# minM3car.net
KiCad netlist of a schematic drawn in EAGLE
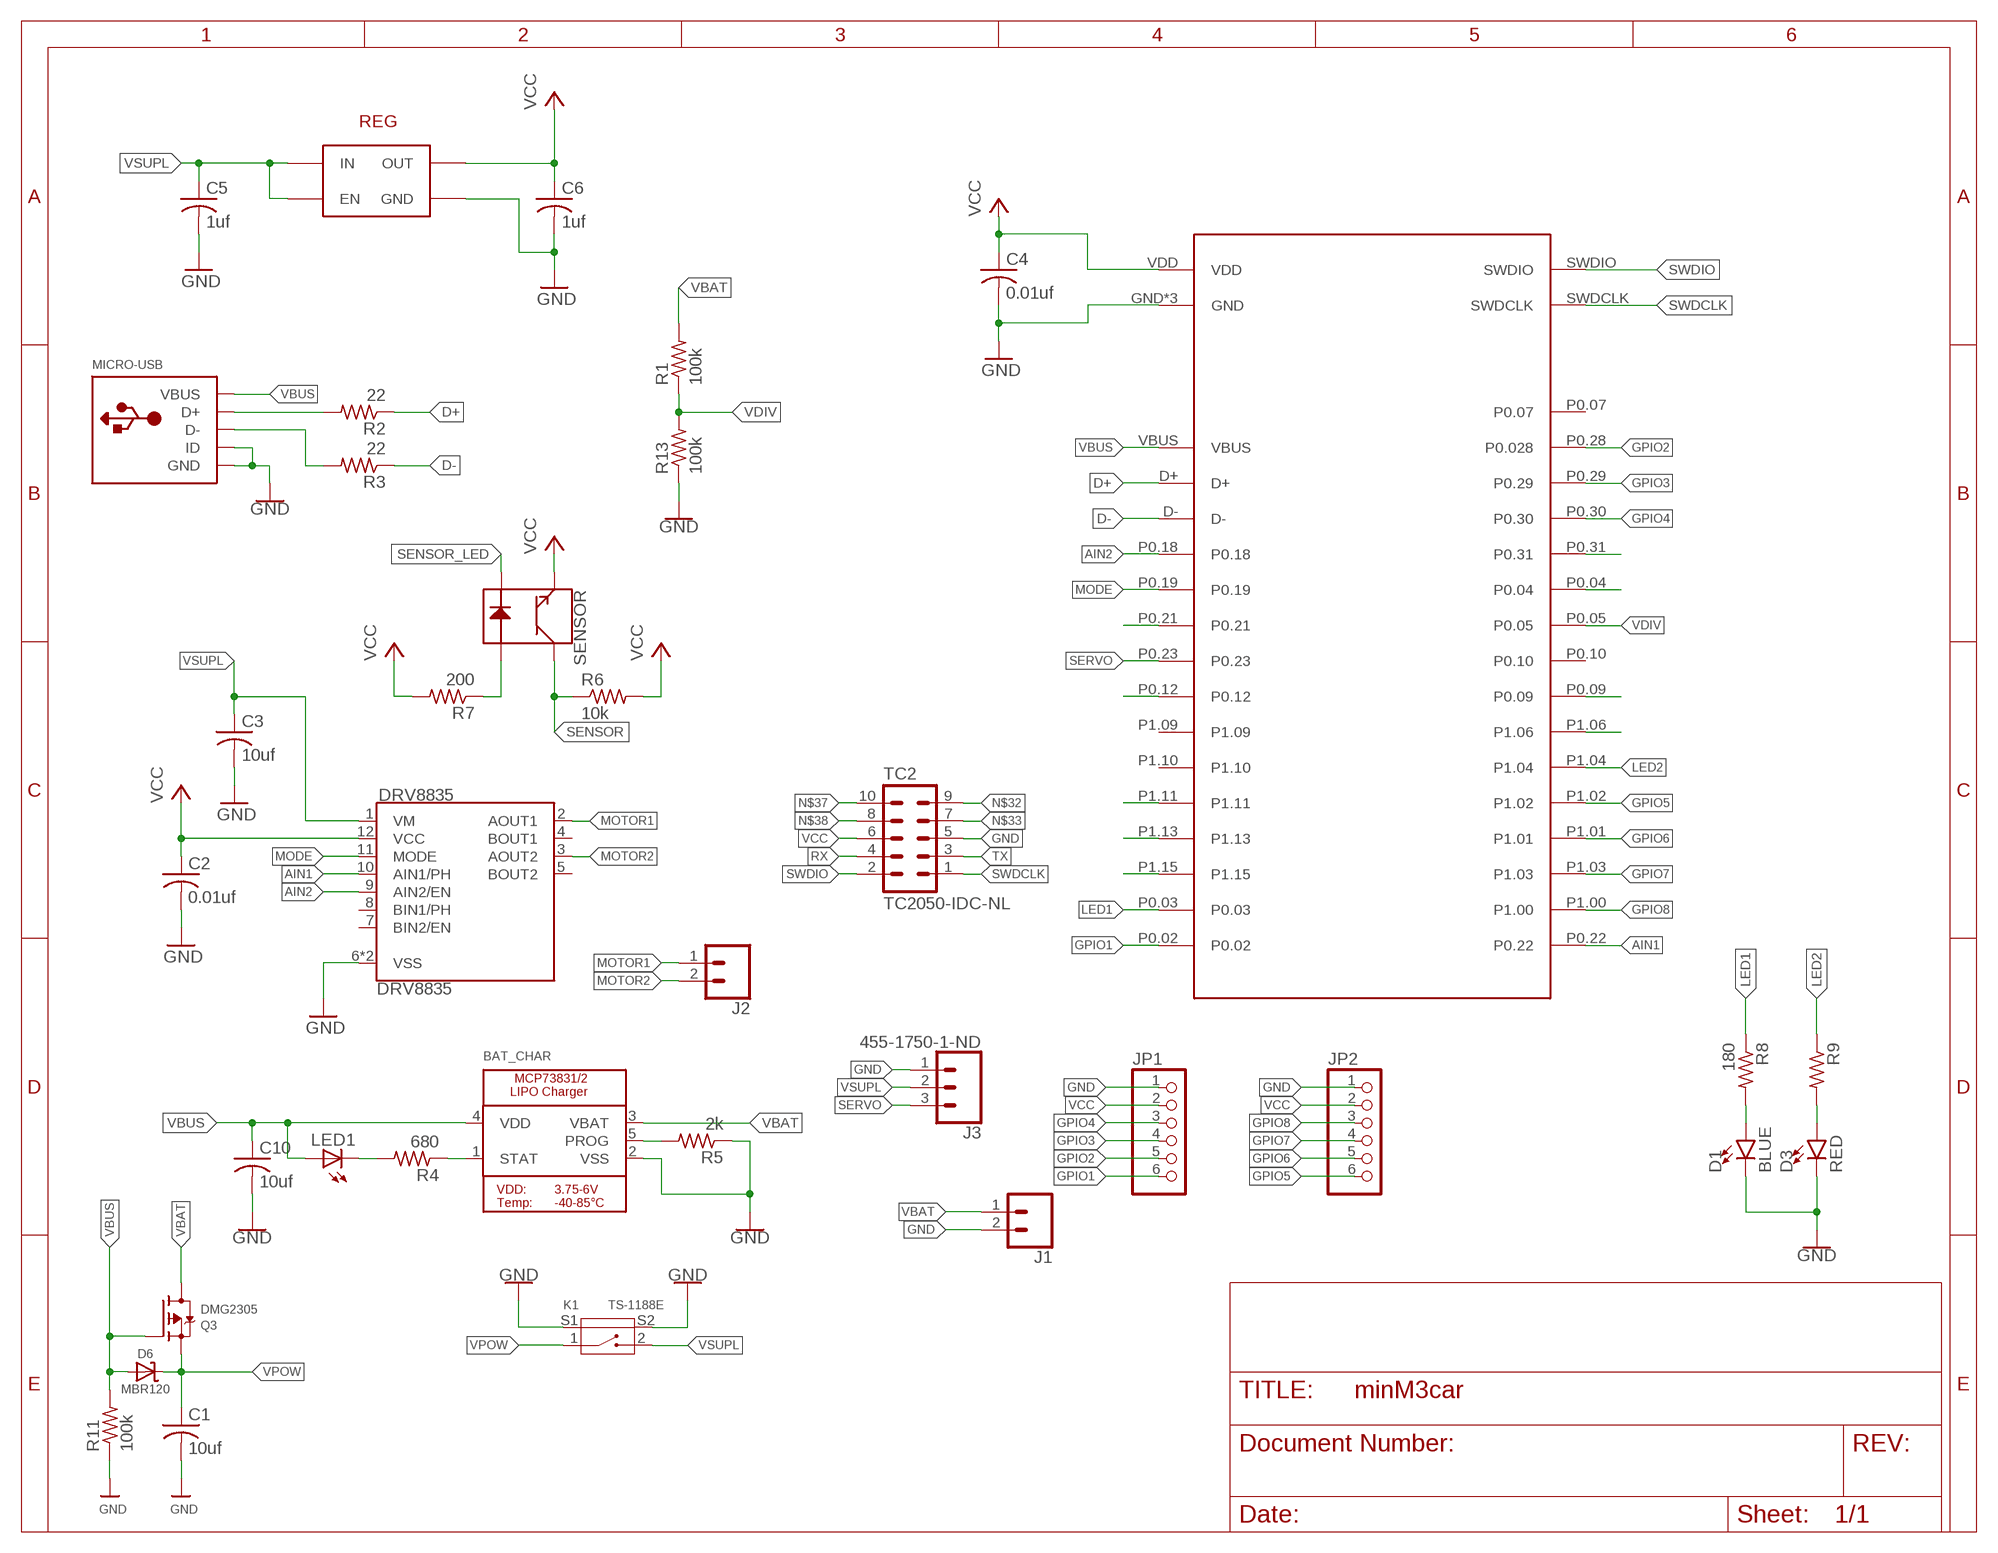
[diagram p0: schematic, sheet 1]

(export (version "E")
  (design (tool "Eeschema 10.0.6"))
  (components
    (comp (ref "BAT_CHAR")
      (value "MICROBUILDER_MCP73831/2")
      (footprint "eagle-import:MICROBUILDER_SOT23-5")
      (fields (field (name "MPN") " MCP73831T-2ACI/OT"))
      (libsource (lib "eagle-import") (part "MICROBUILDER_MCP73831/2"))
    )
    (comp (ref "C1")
      (value "10uf")
      (footprint "eagle-import:C0402")
      (fields (field (name "MPN") "GRM155R60G106ME44D"))
      (libsource (lib "eagle-import") (part "C-USC0402"))
    )
    (comp (ref "C2")
      (value "0.01uf")
      (footprint "eagle-import:C0402")
      (fields (field (name "MPN") "CL05C100JB5NNNC"))
      (libsource (lib "eagle-import") (part "C-USC0402"))
    )
    (comp (ref "C3")
      (value "10uf")
      (footprint "eagle-import:C0402")
      (fields (field (name "MPN") "GRM155R60G106ME44D"))
      (libsource (lib "eagle-import") (part "C-USC0402"))
    )
    (comp (ref "C4")
      (value "0.01uf")
      (footprint "eagle-import:C0402")
      (fields (field (name "MPN") "CL05C100JB5NNNC"))
      (libsource (lib "eagle-import") (part "C-USC0402"))
    )
    (comp (ref "C5")
      (value "1uf")
      (footprint "eagle-import:C0402")
      (fields (field (name "MPN") "CL05A105KP5NNNC"))
      (libsource (lib "eagle-import") (part "C-USC0402"))
    )
    (comp (ref "C6")
      (value "1uf")
      (footprint "eagle-import:C0402")
      (fields (field (name "MPN") "CL05A105KP5NNNC"))
      (libsource (lib "eagle-import") (part "C-USC0402"))
    )
    (comp (ref "C10")
      (value "10uf")
      (footprint "eagle-import:C0402")
      (fields (field (name "MPN") "GRM155R60G106ME44D"))
      (libsource (lib "eagle-import") (part "C-USC0402"))
    )
    (comp (ref "D1")
      (value "BLUE")
      (footprint "eagle-import:LED-0603")
      (fields (field (name "MPN") "150060YS75000"))
      (libsource (lib "eagle-import") (part "LED-BLUE0603"))
    )
    (comp (ref "D3")
      (value "RED")
      (footprint "eagle-import:LED-0603")
      (fields (field (name "MPN") "150060YS75000"))
      (libsource (lib "eagle-import") (part "LED-RED0603"))
    )
    (comp (ref "D6")
      (value "MBR120")
      (footprint "eagle-import:SOD-123")
      (fields (field (name "MPN") "MBR120VLSFT3G"))
      (libsource (lib "eagle-import") (part "DIODE-SCHOTTKYSOD-123"))
    )
    (comp (ref "DRV8835")
      (value "DRV8835")
      (footprint "eagle-import:WSON-12")
      (fields (field (name "MPN") "DRV8835DSSR"))
      (libsource (lib "eagle-import") (part "DRV883X"))
    )
    (comp (ref "J1")
      (value "CONN_02")
      (footprint "eagle-import:1X02")
      (libsource (lib "eagle-import") (part "CONN_02"))
    )
    (comp (ref "J2")
      (value "CONN_02")
      (footprint "eagle-import:1X02")
      (libsource (lib "eagle-import") (part "CONN_02"))
    )
    (comp (ref "J3")
      (value "455-1750-1-ND")
      (footprint "eagle-import:1X03")
      (libsource (lib "eagle-import") (part "CONN_03"))
    )
    (comp (ref "JP1")
      (value "PINHD-1X6")
      (footprint "eagle-import:1X06")
      (libsource (lib "eagle-import") (part "PINHD-1X6"))
    )
    (comp (ref "JP2")
      (value "PINHD-1X6")
      (footprint "eagle-import:1X06")
      (libsource (lib "eagle-import") (part "PINHD-1X6"))
    )
    (comp (ref "K1")
      (value "TS-1188E")
      (footprint "eagle-import:SW4-SMD-7.0X3.5X3.5MM-90D")
      (libsource (lib "eagle-import") (part "SMD-BUTTON(2+2P-7X3.5MM-90D)"))
    )
    (comp (ref "LED1")
      (value "LEDCHIPLED_0603")
      (footprint "eagle-import:CHIPLED_0603")
      (fields (field (name "MPN") "150060GS75000"))
      (libsource (lib "eagle-import") (part "LEDCHIPLED_0603"))
    )
    (comp (ref "MICRO-USB")
      (value "MICROBUILDER_USB_MICRO_20329_V2")
      (footprint "eagle-import:MICROBUILDER_4UCONN_20329_V2")
      (fields (field (name "MPN") "10103592-0001LF "))
      (libsource (lib "eagle-import") (part "MICROBUILDER_USB_MICRO_20329_V2"))
    )
    (comp (ref "NRF52")
      (value "HOLYIOT")
      (footprint "eagle-import:HOLYIOT")
      (fields (field (name "MPN") "113990556"))
      (libsource (lib "eagle-import") (part "HOLYIOT"))
    )
    (comp (ref "Q3")
      (value "DMG2305")
      (footprint "eagle-import:SOT23-R")
      (fields (field (name "MPN") "DMG2305UXQ-7"))
      (libsource (lib "eagle-import") (part "MOSFET-P"))
    )
    (comp (ref "R1")
      (value "100k")
      (footprint "eagle-import:R0402")
      (fields (field (name "MPN") "RC0402JR-07100KL"))
      (libsource (lib "eagle-import") (part "adafruit_420_R-US_R0402"))
    )
    (comp (ref "R2")
      (value "22")
      (footprint "eagle-import:R0402")
      (fields (field (name "MPN") "BLM15BB220SN1D"))
      (libsource (lib "eagle-import") (part "R-US_R0402"))
    )
    (comp (ref "R3")
      (value "22")
      (footprint "eagle-import:R0402")
      (fields (field (name "MPN") "BLM15BB220SN1D"))
      (libsource (lib "eagle-import") (part "R-US_R0402"))
    )
    (comp (ref "R4")
      (value "680")
      (footprint "eagle-import:R0402")
      (fields (field (name "MPN") "RC0402JR-07680RL"))
      (libsource (lib "eagle-import") (part "R-US_R0402"))
    )
    (comp (ref "R5")
      (value "2k")
      (footprint "eagle-import:R0402")
      (fields (field (name "MPN") "RC0402FR-072KL"))
      (libsource (lib "eagle-import") (part "R-US_R0402"))
    )
    (comp (ref "R6")
      (value "10k")
      (footprint "eagle-import:R0402")
      (fields (field (name "MPN") "RC0402JR-0710KL"))
      (libsource (lib "eagle-import") (part "R-US_R0402"))
    )
    (comp (ref "R7")
      (value "200")
      (footprint "eagle-import:R0402")
      (fields (field (name "MPN") "0402WGF2000TCE"))
      (libsource (lib "eagle-import") (part "R-US_R0402"))
    )
    (comp (ref "R8")
      (value "180")
      (footprint "eagle-import:R0402")
      (fields (field (name "MPN") "RC0402FR-07180RL"))
      (libsource (lib "eagle-import") (part "R-US_R0402"))
    )
    (comp (ref "R9")
      (value "180")
      (footprint "eagle-import:R0402")
      (fields (field (name "MPN") "RC0402FR-07180RL"))
      (libsource (lib "eagle-import") (part "R-US_R0402"))
    )
    (comp (ref "R11")
      (value "100k")
      (footprint "eagle-import:R0402")
      (fields (field (name "MPN") "RC0402JR-07100KL"))
      (libsource (lib "eagle-import") (part "adafruit_420_R-US_R0402"))
    )
    (comp (ref "R13")
      (value "100k")
      (footprint "eagle-import:R0402")
      (fields (field (name "MPN") "RC0402JR-07100KL"))
      (libsource (lib "eagle-import") (part "adafruit_420_R-US_R0402"))
    )
    (comp (ref "REG")
      (value "TLV703")
      (footprint "eagle-import:SOT95P285X120-5N")
      (fields (field (name "MPN") "TLV7031DBVR"))
      (libsource (lib "eagle-import") (part "TLV703"))
    )
    (comp (ref "SENSOR")
      (value "QRE1113SMD-W")
      (footprint "eagle-import:QRE1113-W")
      (fields (field (name "MPN") "QRE1113GR"))
      (libsource (lib "eagle-import") (part "QRE1113SMD-W"))
    )
    (comp (ref "TC2")
      (value "TC2050-IDC-NL")
      (footprint "eagle-import:TC2050-IDC-NL")
      (libsource (lib "eagle-import") (part "TC2050-IDC-NL"))
    )
  )
  (nets
    (net (code "1") (name "AIN1") (class "Default")
      (node (ref "DRV8835") (pin "10") (pinfunction "AIN1/PH_10") (pintype "bidirectional"))
      (node (ref "NRF52") (pin "P0.22") (pinfunction "P0.22_P0.22") (pintype "bidirectional"))
    )
    (net (code "2") (name "AIN2") (class "Default")
      (node (ref "DRV8835") (pin "9") (pinfunction "AIN2/EN_9") (pintype "bidirectional"))
      (node (ref "NRF52") (pin "P0.18") (pinfunction "P0.18_P0.18") (pintype "bidirectional"))
    )
    (net (code "3") (name "D+") (class "Default")
      (node (ref "NRF52") (pin "D+") (pinfunction "D+_D+") (pintype "bidirectional"))
      (node (ref "R2") (pin "1") (pinfunction "1_1") (pintype "passive"))
    )
    (net (code "4") (name "D-") (class "Default")
      (node (ref "NRF52") (pin "D-") (pinfunction "D-_D-") (pintype "bidirectional"))
      (node (ref "R3") (pin "1") (pinfunction "1_1") (pintype "passive"))
    )
    (net (code "5") (name "GND") (class "Default")
      (node (ref "BAT_CHAR") (pin "2") (pinfunction "VSS_2") (pintype "power_in"))
      (node (ref "C1") (pin "2") (pinfunction "2_2") (pintype "passive"))
      (node (ref "C10") (pin "2") (pinfunction "2_2") (pintype "passive"))
      (node (ref "C2") (pin "2") (pinfunction "2_2") (pintype "passive"))
      (node (ref "C3") (pin "2") (pinfunction "2_2") (pintype "passive"))
      (node (ref "C4") (pin "2") (pinfunction "2_2") (pintype "passive"))
      (node (ref "C5") (pin "2") (pinfunction "2_2") (pintype "passive"))
      (node (ref "C6") (pin "2") (pinfunction "2_2") (pintype "passive"))
      (node (ref "D1") (pin "C") (pinfunction "C_C") (pintype "passive"))
      (node (ref "D3") (pin "C") (pinfunction "C_C") (pintype "passive"))
      (node (ref "DRV8835") (pin "6") (pinfunction "VSS_6") (pintype "bidirectional"))
      (node (ref "DRV8835") (pin "PAD") (pinfunction "VSS_PAD") (pintype "bidirectional"))
      (node (ref "J1") (pin "2") (pinfunction "2_2") (pintype "passive"))
      (node (ref "J3") (pin "1") (pinfunction "1_1") (pintype "passive"))
      (node (ref "JP1") (pin "1") (pinfunction "1_1") (pintype "passive"))
      (node (ref "JP2") (pin "1") (pinfunction "1_1") (pintype "passive"))
      (node (ref "K1") (pin "S1") (pinfunction "S1_S1") (pintype "bidirectional"))
      (node (ref "K1") (pin "S2") (pinfunction "S2_S2") (pintype "bidirectional"))
      (node (ref "MICRO-USB") (pin "BASE@1") (pinfunction "GND_BASE@1") (pintype "power_in"))
      (node (ref "MICRO-USB") (pin "BASE@2") (pinfunction "GND_BASE@2") (pintype "power_in"))
      (node (ref "MICRO-USB") (pin "GND") (pinfunction "GND_GND") (pintype "power_in"))
      (node (ref "MICRO-USB") (pin "ID") (pinfunction "ID_ID") (pintype "bidirectional"))
      (node (ref "MICRO-USB") (pin "SPRT@1") (pinfunction "GND_SPRT@1") (pintype "power_in"))
      (node (ref "MICRO-USB") (pin "SPRT@2") (pinfunction "GND_SPRT@2") (pintype "power_in"))
      (node (ref "MICRO-USB") (pin "SPRT@3") (pinfunction "GND_SPRT@3") (pintype "power_in"))
      (node (ref "MICRO-USB") (pin "SPRT@4") (pinfunction "GND_SPRT@4") (pintype "power_in"))
      (node (ref "NRF52") (pin "GND") (pinfunction "GND_GND") (pintype "bidirectional"))
      (node (ref "NRF52") (pin "GND2") (pinfunction "GND_GND2") (pintype "bidirectional"))
      (node (ref "NRF52") (pin "GND3") (pinfunction "GND_GND3") (pintype "bidirectional"))
      (node (ref "R11") (pin "1") (pinfunction "1_1") (pintype "passive"))
      (node (ref "R13") (pin "1") (pinfunction "1_1") (pintype "passive"))
      (node (ref "R5") (pin "1") (pinfunction "1_1") (pintype "passive"))
      (node (ref "REG") (pin "2") (pinfunction "GND_2") (pintype "bidirectional"))
      (node (ref "TC2") (pin "5") (pinfunction "5_5") (pintype "passive"))
    )
    (net (code "6") (name "GPIO1") (class "Default")
      (node (ref "JP1") (pin "6") (pinfunction "6_6") (pintype "passive"))
      (node (ref "NRF52") (pin "P0.02") (pinfunction "P0.02_P0.02") (pintype "bidirectional"))
    )
    (net (code "7") (name "GPIO2") (class "Default")
      (node (ref "JP1") (pin "5") (pinfunction "5_5") (pintype "passive"))
      (node (ref "NRF52") (pin "P0.28") (pinfunction "P0.028_P0.28") (pintype "bidirectional"))
    )
    (net (code "8") (name "GPIO3") (class "Default")
      (node (ref "JP1") (pin "4") (pinfunction "4_4") (pintype "passive"))
      (node (ref "NRF52") (pin "P0.29") (pinfunction "P0.29_P0.29") (pintype "bidirectional"))
    )
    (net (code "9") (name "GPIO4") (class "Default")
      (node (ref "JP1") (pin "3") (pinfunction "3_3") (pintype "passive"))
      (node (ref "NRF52") (pin "P0.30") (pinfunction "P0.30_P0.30") (pintype "bidirectional"))
    )
    (net (code "10") (name "GPIO5") (class "Default")
      (node (ref "JP2") (pin "6") (pinfunction "6_6") (pintype "passive"))
      (node (ref "NRF52") (pin "P1.02") (pinfunction "P1.02_P1.02") (pintype "bidirectional"))
    )
    (net (code "11") (name "GPIO6") (class "Default")
      (node (ref "JP2") (pin "5") (pinfunction "5_5") (pintype "passive"))
      (node (ref "NRF52") (pin "P1.01") (pinfunction "P1.01_P1.01") (pintype "bidirectional"))
    )
    (net (code "12") (name "GPIO7") (class "Default")
      (node (ref "JP2") (pin "4") (pinfunction "4_4") (pintype "passive"))
      (node (ref "NRF52") (pin "P1.03") (pinfunction "P1.03_P1.03") (pintype "bidirectional"))
    )
    (net (code "13") (name "GPIO8") (class "Default")
      (node (ref "JP2") (pin "3") (pinfunction "3_3") (pintype "passive"))
      (node (ref "NRF52") (pin "P1.00") (pinfunction "P1.00_P1.00") (pintype "bidirectional"))
    )
    (net (code "14") (name "LED1") (class "Default")
      (node (ref "NRF52") (pin "P0.03") (pinfunction "P0.03_P0.03") (pintype "bidirectional"))
      (node (ref "R8") (pin "1") (pinfunction "1_1") (pintype "passive"))
    )
    (net (code "15") (name "LED2") (class "Default")
      (node (ref "NRF52") (pin "P1.04") (pinfunction "P1.04_P1.04") (pintype "bidirectional"))
      (node (ref "R9") (pin "1") (pinfunction "1_1") (pintype "passive"))
    )
    (net (code "16") (name "MODE") (class "Default")
      (node (ref "DRV8835") (pin "11") (pinfunction "MODE_11") (pintype "bidirectional"))
      (node (ref "NRF52") (pin "P0.19") (pinfunction "P0.19_P0.19") (pintype "bidirectional"))
    )
    (net (code "17") (name "MOTOR1") (class "Default")
      (node (ref "DRV8835") (pin "2") (pinfunction "AOUT1_2") (pintype "bidirectional"))
      (node (ref "J2") (pin "1") (pinfunction "1_1") (pintype "passive"))
    )
    (net (code "18") (name "MOTOR2") (class "Default")
      (node (ref "DRV8835") (pin "3") (pinfunction "AOUT2_3") (pintype "bidirectional"))
      (node (ref "J2") (pin "2") (pinfunction "2_2") (pintype "passive"))
    )
    (net (code "19") (name "N$32") (class "Default")
      (node (ref "TC2") (pin "9") (pinfunction "9_9") (pintype "passive"))
    )
    (net (code "20") (name "N$33") (class "Default")
      (node (ref "TC2") (pin "7") (pinfunction "7_7") (pintype "passive"))
    )
    (net (code "21") (name "N$37") (class "Default")
      (node (ref "TC2") (pin "10") (pinfunction "10_10") (pintype "passive"))
    )
    (net (code "22") (name "N$38") (class "Default")
      (node (ref "TC2") (pin "8") (pinfunction "8_8") (pintype "passive"))
    )
    (net (code "23") (name "Net-(BAT_CHAR-PROG)") (class "Default")
      (node (ref "BAT_CHAR") (pin "5") (pinfunction "PROG_5") (pintype "input"))
      (node (ref "R5") (pin "2") (pinfunction "2_2") (pintype "passive"))
    )
    (net (code "24") (name "Net-(BAT_CHAR-STAT)") (class "Default")
      (node (ref "BAT_CHAR") (pin "1") (pinfunction "STAT_1") (pintype "output"))
      (node (ref "R4") (pin "1") (pinfunction "1_1") (pintype "passive"))
    )
    (net (code "25") (name "Net-(D1-PadA)") (class "Default")
      (node (ref "D1") (pin "A") (pinfunction "A_A") (pintype "passive"))
      (node (ref "R8") (pin "2") (pinfunction "2_2") (pintype "passive"))
    )
    (net (code "26") (name "Net-(D3-PadA)") (class "Default")
      (node (ref "D3") (pin "A") (pinfunction "A_A") (pintype "passive"))
      (node (ref "R9") (pin "2") (pinfunction "2_2") (pintype "passive"))
    )
    (net (code "27") (name "Net-(LED1-PadC)") (class "Default")
      (node (ref "LED1") (pin "C") (pinfunction "C_C") (pintype "passive"))
      (node (ref "R4") (pin "2") (pinfunction "2_2") (pintype "passive"))
    )
    (net (code "28") (name "Net-(MICRO-USB-PadD+)") (class "Default")
      (node (ref "MICRO-USB") (pin "D+") (pinfunction "D+_D+") (pintype "bidirectional"))
      (node (ref "R2") (pin "2") (pinfunction "2_2") (pintype "passive"))
    )
    (net (code "29") (name "Net-(MICRO-USB-PadD-)") (class "Default")
      (node (ref "MICRO-USB") (pin "D-") (pinfunction "D-_D-") (pintype "bidirectional"))
      (node (ref "R3") (pin "2") (pinfunction "2_2") (pintype "passive"))
    )
    (net (code "30") (name "Net-(SENSOR-A)") (class "Default")
      (node (ref "R7") (pin "1") (pinfunction "1_1") (pintype "passive"))
      (node (ref "SENSOR") (pin "1") (pinfunction "A_1") (pintype "bidirectional"))
    )
    (net (code "31") (name "RX") (class "Default")
      (node (ref "TC2") (pin "4") (pinfunction "4_4") (pintype "passive"))
    )
    (net (code "32") (name "SENSOR") (class "Default")
      (node (ref "R6") (pin "1") (pinfunction "1_1") (pintype "passive"))
      (node (ref "SENSOR") (pin "3") (pinfunction "C_3") (pintype "bidirectional"))
    )
    (net (code "33") (name "SENSOR_LED") (class "Default")
      (node (ref "SENSOR") (pin "2") (pinfunction "K_2") (pintype "bidirectional"))
    )
    (net (code "34") (name "SERVO") (class "Default")
      (node (ref "J3") (pin "3") (pinfunction "3_3") (pintype "passive"))
      (node (ref "NRF52") (pin "P0.23") (pinfunction "P0.23_P0.23") (pintype "bidirectional"))
    )
    (net (code "35") (name "SWDCLK") (class "Default")
      (node (ref "NRF52") (pin "SWDCLK") (pinfunction "SWDCLK_SWDCLK") (pintype "bidirectional"))
      (node (ref "TC2") (pin "1") (pinfunction "1_1") (pintype "passive"))
    )
    (net (code "36") (name "SWDIO") (class "Default")
      (node (ref "NRF52") (pin "SWDIO") (pinfunction "SWDIO_SWDIO") (pintype "bidirectional"))
      (node (ref "TC2") (pin "2") (pinfunction "2_2") (pintype "passive"))
    )
    (net (code "37") (name "TX") (class "Default")
      (node (ref "TC2") (pin "3") (pinfunction "3_3") (pintype "passive"))
    )
    (net (code "38") (name "VBAT") (class "Default")
      (node (ref "BAT_CHAR") (pin "3") (pinfunction "VBAT_3") (pintype "power_in"))
      (node (ref "J1") (pin "1") (pinfunction "1_1") (pintype "passive"))
      (node (ref "Q3") (pin "3") (pinfunction "D_3") (pintype "passive"))
      (node (ref "R1") (pin "2") (pinfunction "2_2") (pintype "passive"))
    )
    (net (code "39") (name "VBUS") (class "Default")
      (node (ref "BAT_CHAR") (pin "4") (pinfunction "VDD_4") (pintype "power_in"))
      (node (ref "C10") (pin "1") (pinfunction "1_1") (pintype "passive"))
      (node (ref "D6") (pin "A") (pinfunction "A_A") (pintype "passive"))
      (node (ref "LED1") (pin "A") (pinfunction "A_A") (pintype "passive"))
      (node (ref "MICRO-USB") (pin "VBUS") (pinfunction "VBUS_VBUS") (pintype "power_in"))
      (node (ref "NRF52") (pin "VBUS") (pinfunction "VBUS_VBUS") (pintype "bidirectional"))
      (node (ref "Q3") (pin "1") (pinfunction "G_1") (pintype "passive"))
      (node (ref "R11") (pin "2") (pinfunction "2_2") (pintype "passive"))
    )
    (net (code "40") (name "VCC") (class "Default")
      (node (ref "C2") (pin "1") (pinfunction "1_1") (pintype "passive"))
      (node (ref "C4") (pin "1") (pinfunction "1_1") (pintype "passive"))
      (node (ref "C6") (pin "1") (pinfunction "1_1") (pintype "passive"))
      (node (ref "DRV8835") (pin "12") (pinfunction "VCC_12") (pintype "bidirectional"))
      (node (ref "JP1") (pin "2") (pinfunction "2_2") (pintype "passive"))
      (node (ref "JP2") (pin "2") (pinfunction "2_2") (pintype "passive"))
      (node (ref "NRF52") (pin "VDD") (pinfunction "VDD_VDD") (pintype "bidirectional"))
      (node (ref "R6") (pin "2") (pinfunction "2_2") (pintype "passive"))
      (node (ref "R7") (pin "2") (pinfunction "2_2") (pintype "passive"))
      (node (ref "REG") (pin "5") (pinfunction "OUT_5") (pintype "bidirectional"))
      (node (ref "SENSOR") (pin "4") (pinfunction "E_4") (pintype "bidirectional"))
      (node (ref "TC2") (pin "6") (pinfunction "6_6") (pintype "passive"))
    )
    (net (code "41") (name "VDIV") (class "Default")
      (node (ref "NRF52") (pin "P0.05") (pinfunction "P0.05_P0.05") (pintype "bidirectional"))
      (node (ref "R1") (pin "1") (pinfunction "1_1") (pintype "passive"))
      (node (ref "R13") (pin "2") (pinfunction "2_2") (pintype "passive"))
    )
    (net (code "42") (name "VPOW") (class "Default")
      (node (ref "C1") (pin "1") (pinfunction "1_1") (pintype "passive"))
      (node (ref "D6") (pin "C") (pinfunction "C_C") (pintype "passive"))
      (node (ref "K1") (pin "1") (pinfunction "1_1") (pintype "bidirectional"))
      (node (ref "Q3") (pin "2") (pinfunction "S_2") (pintype "passive"))
    )
    (net (code "43") (name "VSUPL") (class "Default")
      (node (ref "C3") (pin "1") (pinfunction "1_1") (pintype "passive"))
      (node (ref "C5") (pin "1") (pinfunction "1_1") (pintype "passive"))
      (node (ref "DRV8835") (pin "1") (pinfunction "VM_1") (pintype "bidirectional"))
      (node (ref "J3") (pin "2") (pinfunction "2_2") (pintype "passive"))
      (node (ref "K1") (pin "2") (pinfunction "2_2") (pintype "bidirectional"))
      (node (ref "REG") (pin "1") (pinfunction "IN_1") (pintype "bidirectional"))
      (node (ref "REG") (pin "3") (pinfunction "EN_3") (pintype "bidirectional"))
    )
    (net (code "44") (name "unconnected-(DRV8835-BIN1{slash}PH-Pad8)") (class "Default")
      (node (ref "DRV8835") (pin "8") (pinfunction "BIN1/PH_8") (pintype "bidirectional"))
    )
    (net (code "45") (name "unconnected-(DRV8835-BIN2{slash}EN-Pad7)") (class "Default")
      (node (ref "DRV8835") (pin "7") (pinfunction "BIN2/EN_7") (pintype "bidirectional"))
    )
    (net (code "46") (name "unconnected-(DRV8835-BOUT1-Pad4)") (class "Default")
      (node (ref "DRV8835") (pin "4") (pinfunction "BOUT1_4") (pintype "bidirectional"))
    )
    (net (code "47") (name "unconnected-(DRV8835-BOUT2-Pad5)") (class "Default")
      (node (ref "DRV8835") (pin "5") (pinfunction "BOUT2_5") (pintype "bidirectional"))
    )
    (net (code "48") (name "unconnected-(NRF52-PadP0.04)") (class "Default")
      (node (ref "NRF52") (pin "P0.04") (pinfunction "P0.04_P0.04") (pintype "bidirectional"))
    )
    (net (code "49") (name "unconnected-(NRF52-PadP0.07)") (class "Default")
      (node (ref "NRF52") (pin "P0.07") (pinfunction "P0.07_P0.07") (pintype "bidirectional"))
    )
    (net (code "50") (name "unconnected-(NRF52-PadP0.09)") (class "Default")
      (node (ref "NRF52") (pin "P0.09") (pinfunction "P0.09_P0.09") (pintype "bidirectional"))
    )
    (net (code "51") (name "unconnected-(NRF52-PadP0.10)") (class "Default")
      (node (ref "NRF52") (pin "P0.10") (pinfunction "P0.10_P0.10") (pintype "bidirectional"))
    )
    (net (code "52") (name "unconnected-(NRF52-PadP0.12)") (class "Default")
      (node (ref "NRF52") (pin "P0.12") (pinfunction "P0.12_P0.12") (pintype "bidirectional"))
    )
    (net (code "53") (name "unconnected-(NRF52-PadP0.21)") (class "Default")
      (node (ref "NRF52") (pin "P0.21") (pinfunction "P0.21_P0.21") (pintype "bidirectional"))
    )
    (net (code "54") (name "unconnected-(NRF52-PadP0.31)") (class "Default")
      (node (ref "NRF52") (pin "P0.31") (pinfunction "P0.31_P0.31") (pintype "bidirectional"))
    )
    (net (code "55") (name "unconnected-(NRF52-PadP1.06)") (class "Default")
      (node (ref "NRF52") (pin "P1.06") (pinfunction "P1.06_P1.06") (pintype "bidirectional"))
    )
    (net (code "56") (name "unconnected-(NRF52-PadP1.09)") (class "Default")
      (node (ref "NRF52") (pin "P1.09") (pinfunction "P1.09_P1.09") (pintype "bidirectional"))
    )
    (net (code "57") (name "unconnected-(NRF52-PadP1.10)") (class "Default")
      (node (ref "NRF52") (pin "P1.10") (pinfunction "P1.10_P1.10") (pintype "bidirectional"))
    )
    (net (code "58") (name "unconnected-(NRF52-PadP1.11)") (class "Default")
      (node (ref "NRF52") (pin "P1.11") (pinfunction "P1.11_P1.11") (pintype "bidirectional"))
    )
    (net (code "59") (name "unconnected-(NRF52-PadP1.13)") (class "Default")
      (node (ref "NRF52") (pin "P1.13") (pinfunction "P1.13_P1.13") (pintype "bidirectional"))
    )
    (net (code "60") (name "unconnected-(NRF52-PadP1.15)") (class "Default")
      (node (ref "NRF52") (pin "P1.15") (pinfunction "P1.15_P1.15") (pintype "bidirectional"))
    )
  )
)
